# Power.net
KiCad netlist of a schematic drawn in Altium Designer
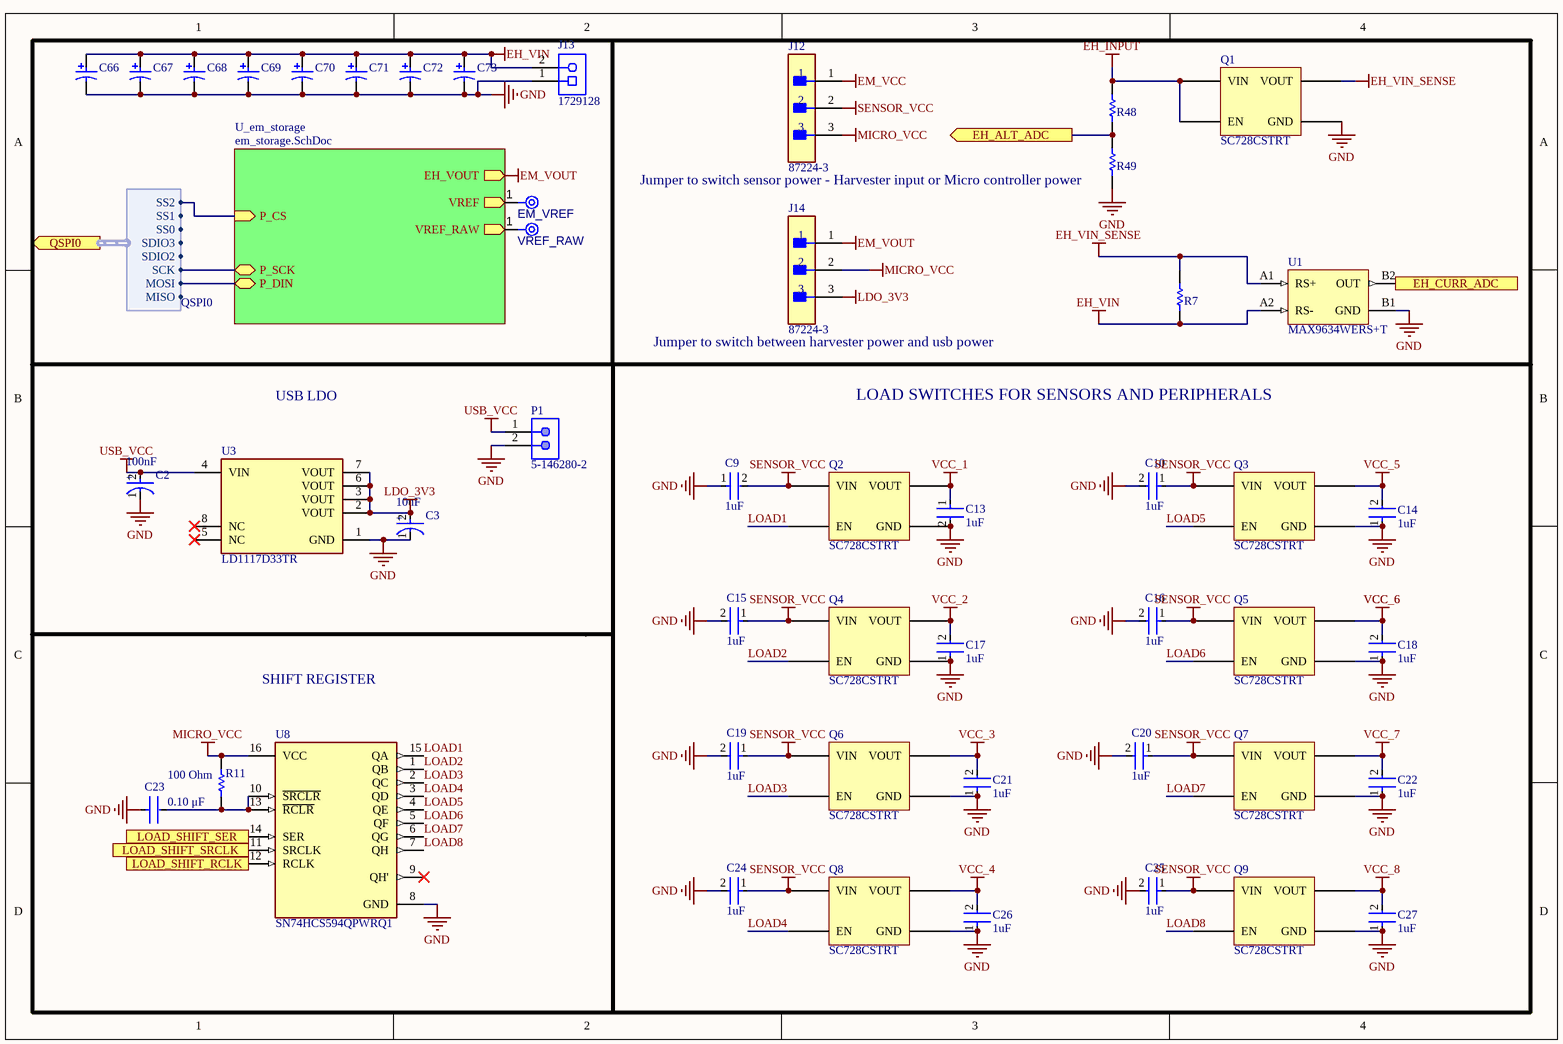
[diagram p0: Power.SchDoc]

(export (version "E")
  (design (tool "Eeschema 10.0.6"))
  (components
    (comp (ref "C2")
      (value "T491A104K035AT")
      (footprint "FP-T491A104K035AT-MFG")
      (description "CAP TANT 0.1UF 10% 35V 1206")
      (fields
        (field (name "TOLERANCE") "10%")
        (field (name "VOLTAGE") "35V")
        (field (name "CAPACITANCE") "100nF")
      )
      (libsource (lib "Altium Content Vault") (part "a00bbbee19879c290e62620ae7e47b1"))
    )
    (comp (ref "C3")
      (value "TAJA106K006RNJ")
      (footprint "FP-TAJA-MFG")
      (description "10uF 6.3V  ±10% 4Ω 1206  SMD Tantalum Capacitor")
      (fields
        (field (name "CAPACITANCE") "10uF")
        (field (name "VOLTAGE") "6.3V")
        (field (name "TOLERANCE") "20%")
      )
      (libsource (lib "Altium Content Vault") (part "203bc49f2ac43e59fd269a8c329ed05"))
    )
    (comp (ref "C9")
      (value "GRT155R61C105KE01J")
      (footprint "FP-GRM15-0_1-MFG")
      (description "CAP CER 1UF 10V X5R 0402")
      (fields
        (field (name "OCTOPART") "https://octopart.com/grm155r61a105ke15d-murata-197442")
        (field (name "MANUFACTURER PART NUMBER") "GRM155R61A105KE15D")
        (field (name "CAPACITANCE") "1uF")
      )
      (libsource (lib "Altium Content Vault") (part "02cd4be3c70576c341d710602a673aa"))
    )
    (comp (ref "C10")
      (value "GRT155R61C105KE01J")
      (footprint "FP-GRM15-0_1-MFG")
      (description "CAP CER 1UF 10V X5R 0402")
      (fields
        (field (name "OCTOPART") "https://octopart.com/grm155r61a105ke15d-murata-197442")
        (field (name "MANUFACTURER PART NUMBER") "GRM155R61A105KE15D")
        (field (name "CAPACITANCE") "1uF")
      )
      (libsource (lib "Altium Content Vault") (part "02cd4be3c70576c341d710602a673aa"))
    )
    (comp (ref "C13")
      (value "GRT155R61C105KE01J")
      (footprint "FP-GRM15-0_1-MFG")
      (description "CAP CER 1UF 10V X5R 0402")
      (fields
        (field (name "OCTOPART") "https://octopart.com/grm155r61a105ke15d-murata-197442")
        (field (name "MANUFACTURER PART NUMBER") "GRM155R61A105KE15D")
        (field (name "CAPACITANCE") "1uF")
      )
      (libsource (lib "Altium Content Vault") (part "02cd4be3c70576c341d710602a673aa"))
    )
    (comp (ref "C14")
      (value "GRT155R61C105KE01J")
      (footprint "FP-GRM15-0_1-MFG")
      (description "CAP CER 1UF 10V X5R 0402")
      (fields
        (field (name "OCTOPART") "https://octopart.com/grm155r61a105ke15d-murata-197442")
        (field (name "MANUFACTURER PART NUMBER") "GRM155R61A105KE15D")
        (field (name "CAPACITANCE") "1uF")
      )
      (libsource (lib "Altium Content Vault") (part "02cd4be3c70576c341d710602a673aa"))
    )
    (comp (ref "C15")
      (value "GRT155R61C105KE01J")
      (footprint "FP-GRM15-0_1-MFG")
      (description "CAP CER 1UF 10V X5R 0402")
      (fields
        (field (name "OCTOPART") "https://octopart.com/grm155r61a105ke15d-murata-197442")
        (field (name "MANUFACTURER PART NUMBER") "GRM155R61A105KE15D")
        (field (name "CAPACITANCE") "1uF")
      )
      (libsource (lib "Altium Content Vault") (part "02cd4be3c70576c341d710602a673aa"))
    )
    (comp (ref "C16")
      (value "GRT155R61C105KE01J")
      (footprint "FP-GRM15-0_1-MFG")
      (description "CAP CER 1UF 10V X5R 0402")
      (fields
        (field (name "OCTOPART") "https://octopart.com/grm155r61a105ke15d-murata-197442")
        (field (name "MANUFACTURER PART NUMBER") "GRM155R61A105KE15D")
        (field (name "CAPACITANCE") "1uF")
      )
      (libsource (lib "Altium Content Vault") (part "02cd4be3c70576c341d710602a673aa"))
    )
    (comp (ref "C17")
      (value "GRT155R61C105KE01J")
      (footprint "FP-GRM15-0_1-MFG")
      (description "CAP CER 1UF 10V X5R 0402")
      (fields
        (field (name "OCTOPART") "https://octopart.com/grm155r61a105ke15d-murata-197442")
        (field (name "MANUFACTURER PART NUMBER") "GRM155R61A105KE15D")
        (field (name "CAPACITANCE") "1uF")
      )
      (libsource (lib "Altium Content Vault") (part "02cd4be3c70576c341d710602a673aa"))
    )
    (comp (ref "C18")
      (value "GRT155R61C105KE01J")
      (footprint "FP-GRM15-0_1-MFG")
      (description "CAP CER 1UF 10V X5R 0402")
      (fields
        (field (name "OCTOPART") "https://octopart.com/grm155r61a105ke15d-murata-197442")
        (field (name "MANUFACTURER PART NUMBER") "GRM155R61A105KE15D")
        (field (name "CAPACITANCE") "1uF")
      )
      (libsource (lib "Altium Content Vault") (part "02cd4be3c70576c341d710602a673aa"))
    )
    (comp (ref "C19")
      (value "GRT155R61C105KE01J")
      (footprint "FP-GRM15-0_1-MFG")
      (description "CAP CER 1UF 10V X5R 0402")
      (fields
        (field (name "OCTOPART") "https://octopart.com/grm155r61a105ke15d-murata-197442")
        (field (name "MANUFACTURER PART NUMBER") "GRM155R61A105KE15D")
        (field (name "CAPACITANCE") "1uF")
      )
      (libsource (lib "Altium Content Vault") (part "02cd4be3c70576c341d710602a673aa"))
    )
    (comp (ref "C20")
      (value "GRT155R61C105KE01J")
      (footprint "FP-GRM15-0_1-MFG")
      (description "CAP CER 1UF 10V X5R 0402")
      (fields
        (field (name "OCTOPART") "https://octopart.com/grm155r61a105ke15d-murata-197442")
        (field (name "MANUFACTURER PART NUMBER") "GRM155R61A105KE15D")
        (field (name "CAPACITANCE") "1uF")
      )
      (libsource (lib "Altium Content Vault") (part "02cd4be3c70576c341d710602a673aa"))
    )
    (comp (ref "C21")
      (value "GRT155R61C105KE01J")
      (footprint "FP-GRM15-0_1-MFG")
      (description "CAP CER 1UF 10V X5R 0402")
      (fields
        (field (name "OCTOPART") "https://octopart.com/grm155r61a105ke15d-murata-197442")
        (field (name "MANUFACTURER PART NUMBER") "GRM155R61A105KE15D")
        (field (name "CAPACITANCE") "1uF")
      )
      (libsource (lib "Altium Content Vault") (part "02cd4be3c70576c341d710602a673aa"))
    )
    (comp (ref "C22")
      (value "GRT155R61C105KE01J")
      (footprint "FP-GRM15-0_1-MFG")
      (description "CAP CER 1UF 10V X5R 0402")
      (fields
        (field (name "OCTOPART") "https://octopart.com/grm155r61a105ke15d-murata-197442")
        (field (name "MANUFACTURER PART NUMBER") "GRM155R61A105KE15D")
        (field (name "CAPACITANCE") "1uF")
      )
      (libsource (lib "Altium Content Vault") (part "02cd4be3c70576c341d710602a673aa"))
    )
    (comp (ref "C23")
      (value "C0402C104K8PACTU")
      (footprint "FP-C0402-BB-MFG")
      (description "CAP CER 0.1UF 10V X5R 0402")
      (fields
        (field (name "CAPACITANCE") "0.10 μF")
        (field (name "MANUFACTURER") "Kemet")
        (field (name "TOLERANCE") "0.1")
      )
      (libsource (lib "Altium Content Vault") (part "b4654b650e69147ec39a6b967a45e02"))
    )
    (comp (ref "C24")
      (value "GRT155R61C105KE01J")
      (footprint "FP-GRM15-0_1-MFG")
      (description "CAP CER 1UF 10V X5R 0402")
      (fields
        (field (name "OCTOPART") "https://octopart.com/grm155r61a105ke15d-murata-197442")
        (field (name "MANUFACTURER PART NUMBER") "GRM155R61A105KE15D")
        (field (name "CAPACITANCE") "1uF")
      )
      (libsource (lib "Altium Content Vault") (part "02cd4be3c70576c341d710602a673aa"))
    )
    (comp (ref "C25")
      (value "GRT155R61C105KE01J")
      (footprint "FP-GRM15-0_1-MFG")
      (description "CAP CER 1UF 10V X5R 0402")
      (fields
        (field (name "OCTOPART") "https://octopart.com/grm155r61a105ke15d-murata-197442")
        (field (name "MANUFACTURER PART NUMBER") "GRM155R61A105KE15D")
        (field (name "CAPACITANCE") "1uF")
      )
      (libsource (lib "Altium Content Vault") (part "02cd4be3c70576c341d710602a673aa"))
    )
    (comp (ref "C26")
      (value "GRT155R61C105KE01J")
      (footprint "FP-GRM15-0_1-MFG")
      (description "CAP CER 1UF 10V X5R 0402")
      (fields
        (field (name "OCTOPART") "https://octopart.com/grm155r61a105ke15d-murata-197442")
        (field (name "MANUFACTURER PART NUMBER") "GRM155R61A105KE15D")
        (field (name "CAPACITANCE") "1uF")
      )
      (libsource (lib "Altium Content Vault") (part "02cd4be3c70576c341d710602a673aa"))
    )
    (comp (ref "C27")
      (value "GRT155R61C105KE01J")
      (footprint "FP-GRM15-0_1-MFG")
      (description "CAP CER 1UF 10V X5R 0402")
      (fields
        (field (name "OCTOPART") "https://octopart.com/grm155r61a105ke15d-murata-197442")
        (field (name "MANUFACTURER PART NUMBER") "GRM155R61A105KE15D")
        (field (name "CAPACITANCE") "1uF")
      )
      (libsource (lib "Altium Content Vault") (part "02cd4be3c70576c341d710602a673aa"))
    )
    (comp (ref "C66")
      (value "T491D106K025AT")
      (footprint "KEMT-T491-D_L")
      (description "Tantalum Capacitor, 10 uF, +/- 10%, 25 V, -55 to 125 degC, 2-Pin SMD, RoHS, Tape and Reel")
      (fields (field (name "MANUFACTURER") "Kemet") (field (name "VOLTAGE") "25VDC"))
      (libsource (lib "Altium Content Vault") (part "CAP-P-2"))
    )
    (comp (ref "C67")
      (value "T491D106K025AT")
      (footprint "KEMT-T491-D_L")
      (description "Tantalum Capacitor, 10 uF, +/- 10%, 25 V, -55 to 125 degC, 2-Pin SMD, RoHS, Tape and Reel")
      (fields (field (name "MANUFACTURER") "Kemet") (field (name "VOLTAGE") "25VDC"))
      (libsource (lib "Altium Content Vault") (part "CAP-P-2"))
    )
    (comp (ref "C68")
      (value "T491D106K025AT")
      (footprint "KEMT-T491-D_L")
      (description "Tantalum Capacitor, 10 uF, +/- 10%, 25 V, -55 to 125 degC, 2-Pin SMD, RoHS, Tape and Reel")
      (fields (field (name "MANUFACTURER") "Kemet") (field (name "VOLTAGE") "25VDC"))
      (libsource (lib "Altium Content Vault") (part "CAP-P-2"))
    )
    (comp (ref "C69")
      (value "T491D106K025AT")
      (footprint "KEMT-T491-D_L")
      (description "Tantalum Capacitor, 10 uF, +/- 10%, 25 V, -55 to 125 degC, 2-Pin SMD, RoHS, Tape and Reel")
      (fields (field (name "MANUFACTURER") "Kemet") (field (name "VOLTAGE") "25VDC"))
      (libsource (lib "Altium Content Vault") (part "CAP-P-2"))
    )
    (comp (ref "C70")
      (value "T491D106K025AT")
      (footprint "KEMT-T491-D_L")
      (description "Tantalum Capacitor, 10 uF, +/- 10%, 25 V, -55 to 125 degC, 2-Pin SMD, RoHS, Tape and Reel")
      (fields (field (name "MANUFACTURER") "Kemet") (field (name "VOLTAGE") "25VDC"))
      (libsource (lib "Altium Content Vault") (part "CAP-P-2"))
    )
    (comp (ref "C71")
      (value "T491D106K025AT")
      (footprint "KEMT-T491-D_L")
      (description "Tantalum Capacitor, 10 uF, +/- 10%, 25 V, -55 to 125 degC, 2-Pin SMD, RoHS, Tape and Reel")
      (fields (field (name "MANUFACTURER") "Kemet") (field (name "VOLTAGE") "25VDC"))
      (libsource (lib "Altium Content Vault") (part "CAP-P-2"))
    )
    (comp (ref "C72")
      (value "T491D106K025AT")
      (footprint "KEMT-T491-D_L")
      (description "Tantalum Capacitor, 10 uF, +/- 10%, 25 V, -55 to 125 degC, 2-Pin SMD, RoHS, Tape and Reel")
      (fields (field (name "MANUFACTURER") "Kemet") (field (name "VOLTAGE") "25VDC"))
      (libsource (lib "Altium Content Vault") (part "CAP-P-2"))
    )
    (comp (ref "C73")
      (value "T491D106K025AT")
      (footprint "KEMT-T491-D_L")
      (description "Tantalum Capacitor, 10 uF, +/- 10%, 25 V, -55 to 125 degC, 2-Pin SMD, RoHS, Tape and Reel")
      (fields (field (name "MANUFACTURER") "Kemet") (field (name "VOLTAGE") "25VDC"))
      (libsource (lib "Altium Content Vault") (part "CAP-P-2"))
    )
    (comp (ref "EM_VREF")
      (value "TPAD6R")
      (footprint "TP06R")
      (description "0.6mm round")
      (libsource (lib "Supersensor") (part "CMP-001-0001-4"))
    )
    (comp (ref "J12")
      (value "87224-3")
      (footprint "FP-87224-3-MFG")
      (description "CONN HEADER VERT 3POS 2.54MM")
      (libsource (lib "Altium Content Vault") (part "0d3f023dd272f625e17a2be33dea85f"))
    )
    (comp (ref "J13")
      (value "1729128")
      (footprint "PHOE-1729128-2_V")
      (description "PCB Terminal Block, 13.5 A, 400 V, 2-Pin THD, RoHS, Bulk")
      (fields (field (name "MANUFACTURER") "Phoenix Contact"))
      (libsource (lib "Altium Content Vault") (part "CN-2P-F-R2"))
    )
    (comp (ref "J14")
      (value "87224-3")
      (footprint "FP-87224-3-MFG")
      (description "CONN HEADER VERT 3POS 2.54MM")
      (libsource (lib "Altium Content Vault") (part "0d3f023dd272f625e17a2be33dea85f"))
    )
    (comp (ref "P1")
      (value "5-146280-2")
      (footprint "TECO-5-146280-2_V")
      (fields (field (name "MANUFACTURER") "TE Connectivity"))
      (libsource (lib "Altium Content Vault") (part "CN-1P-M-R2"))
    )
    (comp (ref "Q1")
      (value "SC728CSTRT")
      (footprint "PCBComponent_1")
      (libsource (lib "Integrated_Library1") (part "SC728CSTRT"))
    )
    (comp (ref "Q2")
      (value "SC728CSTRT")
      (footprint "PCBComponent_1")
      (libsource (lib "Integrated_Library1") (part "SC728CSTRT"))
    )
    (comp (ref "Q3")
      (value "SC728CSTRT")
      (footprint "PCBComponent_1")
      (libsource (lib "Integrated_Library1") (part "SC728CSTRT"))
    )
    (comp (ref "Q4")
      (value "SC728CSTRT")
      (footprint "PCBComponent_1")
      (libsource (lib "Integrated_Library1") (part "SC728CSTRT"))
    )
    (comp (ref "Q5")
      (value "SC728CSTRT")
      (footprint "PCBComponent_1")
      (libsource (lib "Integrated_Library1") (part "SC728CSTRT"))
    )
    (comp (ref "Q6")
      (value "SC728CSTRT")
      (footprint "PCBComponent_1")
      (libsource (lib "Integrated_Library1") (part "SC728CSTRT"))
    )
    (comp (ref "Q7")
      (value "SC728CSTRT")
      (footprint "PCBComponent_1")
      (libsource (lib "Integrated_Library1") (part "SC728CSTRT"))
    )
    (comp (ref "Q8")
      (value "SC728CSTRT")
      (footprint "PCBComponent_1")
      (libsource (lib "Integrated_Library1") (part "SC728CSTRT"))
    )
    (comp (ref "Q9")
      (value "SC728CSTRT")
      (footprint "PCBComponent_1")
      (libsource (lib "Integrated_Library1") (part "SC728CSTRT"))
    )
    (comp (ref "R7")
      (value "WSL0603R0300FEA18")
      (footprint "RESC1508X46X38ML25T25")
      (fields (field (name "MANUFACTURER") "Vishay Dale"))
      (libsource (lib "Altium Content Vault") (part "RES"))
    )
    (comp (ref "R11")
      (value "ERJ-2RKF1000X")
      (footprint "RESC1005X40X25LL05T05")
      (description "Chip Resistor, 100 Ohm, +/- 1%, 100 mW, -55 to 155 degC, 0402 (1005 Metric), RoHS, Tape and Reel")
      (fields
        (field (name "MANUFACTURER") "Basic Passives")
        (field (name "TOLERANCE") "1%")
        (field (name "RESISTANCE") "100 Ohm")
      )
      (libsource (lib "Altium Content Vault") (part "RES-2"))
    )
    (comp (ref "R48")
      (value "RC0402FR-071ML")
      (footprint "RESC1005X40X25NL05T10")
      (description "3M ohm")
      (fields (field (name "MANUFACTURER") "Yageo / Phycomp"))
      (libsource (lib "Altium Content Vault") (part "RES"))
    )
    (comp (ref "R49")
      (value "RC0402FR-071ML")
      (footprint "RESC1005X40X25NL05T10")
      (description "1M ohm")
      (fields (field (name "MANUFACTURER") "Yageo / Phycomp"))
      (libsource (lib "Altium Content Vault") (part "RES"))
    )
    (comp (ref "U1")
      (value "MAX9634WERS+T")
      (footprint "MAXM-R41A1+1")
      (libsource (lib "Altium Content Vault") (part "MAX9938_9634-X4"))
    )
    (comp (ref "U3")
      (value "LD1117D33TR")
      (footprint "FP-SO-8-0016023-MFG")
      (description "IC REG LINEAR 3.3V 800MA 8SO")
      (libsource (lib "Altium Content Vault") (part "79f2e125495cf94f2011e209b176133"))
    )
    (comp (ref "U8")
      (value "SN74HCS594QPWRQ1")
      (footprint "FP-PW0016A-IPC_A")
      (description "AUTOMOTIVE 8-BIT SHIFT REGISTERS")
      (libsource (lib "Altium Content Vault") (part "ee4c9120f52ff91501c7aa2bff67eb2"))
    )
    (comp (ref "VREF_RAW")
      (value "TPAD6R")
      (footprint "TP06R")
      (description "0.6mm round")
      (libsource (lib "Supersensor") (part "CMP-001-0001-4"))
    )
  )
  (nets
    (net (code "2") (name "/EH_ALT_ADC") (class "Default")
      (node (ref "R48") (pin "1") (pinfunction "1_1") (pintype "passive"))
      (node (ref "R49") (pin "2") (pinfunction "2_2") (pintype "passive"))
    )
    (net (code "3") (name "/EH_CURR_ADC") (class "Default")
      (node (ref "U1") (pin "B2") (pinfunction "OUT_B2") (pintype "output"))
    )
    (net (code "4") (name "/LOAD1") (class "Default")
      (node (ref "Q2") (pin "B2") (pinfunction "EN_B2") (pintype "passive"))
      (node (ref "U8") (pin "15") (pinfunction "QA_15") (pintype "output"))
    )
    (net (code "5") (name "/LOAD2") (class "Default")
      (node (ref "Q4") (pin "B2") (pinfunction "EN_B2") (pintype "passive"))
      (node (ref "U8") (pin "1") (pinfunction "QB_1") (pintype "output"))
    )
    (net (code "6") (name "/LOAD3") (class "Default")
      (node (ref "Q6") (pin "B2") (pinfunction "EN_B2") (pintype "passive"))
      (node (ref "U8") (pin "2") (pinfunction "QC_2") (pintype "output"))
    )
    (net (code "7") (name "/LOAD4") (class "Default")
      (node (ref "Q8") (pin "B2") (pinfunction "EN_B2") (pintype "passive"))
      (node (ref "U8") (pin "3") (pinfunction "QD_3") (pintype "output"))
    )
    (net (code "8") (name "/LOAD5") (class "Default")
      (node (ref "Q3") (pin "B2") (pinfunction "EN_B2") (pintype "passive"))
      (node (ref "U8") (pin "4") (pinfunction "QE_4") (pintype "output"))
    )
    (net (code "9") (name "/LOAD6") (class "Default")
      (node (ref "Q5") (pin "B2") (pinfunction "EN_B2") (pintype "passive"))
      (node (ref "U8") (pin "5") (pinfunction "QF_5") (pintype "output"))
    )
    (net (code "10") (name "/LOAD7") (class "Default")
      (node (ref "Q7") (pin "B2") (pinfunction "EN_B2") (pintype "passive"))
      (node (ref "U8") (pin "6") (pinfunction "QG_6") (pintype "output"))
    )
    (net (code "11") (name "/LOAD8") (class "Default")
      (node (ref "Q9") (pin "B2") (pinfunction "EN_B2") (pintype "passive"))
      (node (ref "U8") (pin "7") (pinfunction "QH_7") (pintype "output"))
    )
    (net (code "12") (name "/LOAD_SHIFT_RCLK") (class "Default")
      (node (ref "U8") (pin "12") (pinfunction "RCLK_12") (pintype "input"))
    )
    (net (code "13") (name "/LOAD_SHIFT_SER") (class "Default")
      (node (ref "U8") (pin "14") (pinfunction "SER_14") (pintype "input"))
    )
    (net (code "14") (name "/LOAD_SHIFT_SRCLK") (class "Default")
      (node (ref "U8") (pin "11") (pinfunction "SRCLK_11") (pintype "input"))
    )
    (net (code "18") (name "/VREF") (class "Default")
      (node (ref "EM_VREF") (pin "1") (pinfunction "TP_1") (pintype "passive"))
    )
    (net (code "19") (name "/VREF_RAW") (class "Default")
      (node (ref "VREF_RAW") (pin "1") (pinfunction "TP_1") (pintype "passive"))
    )
    (net (code "21") (name "EH_INPUT") (class "Default")
      (node (ref "Q1") (pin "A2") (pinfunction "VIN_A2") (pintype "passive"))
      (node (ref "Q1") (pin "B2") (pinfunction "EN_B2") (pintype "passive"))
      (node (ref "R48") (pin "2") (pinfunction "2_2") (pintype "passive"))
    )
    (net (code "22") (name "EH_VIN") (class "Default")
      (node (ref "C66") (pin "1") (pinfunction "1_1") (pintype "passive"))
      (node (ref "C67") (pin "1") (pinfunction "1_1") (pintype "passive"))
      (node (ref "C68") (pin "1") (pinfunction "1_1") (pintype "passive"))
      (node (ref "C69") (pin "1") (pinfunction "1_1") (pintype "passive"))
      (node (ref "C70") (pin "1") (pinfunction "1_1") (pintype "passive"))
      (node (ref "C71") (pin "1") (pinfunction "1_1") (pintype "passive"))
      (node (ref "C72") (pin "1") (pinfunction "1_1") (pintype "passive"))
      (node (ref "C73") (pin "1") (pinfunction "1_1") (pintype "passive"))
      (node (ref "J13") (pin "2") (pinfunction "2_2") (pintype "passive"))
      (node (ref "R7") (pin "1") (pinfunction "1_1") (pintype "passive"))
      (node (ref "U1") (pin "A2") (pinfunction "RS-_A2") (pintype "input"))
    )
    (net (code "23") (name "EH_VIN_SENSE") (class "Default")
      (node (ref "Q1") (pin "A1") (pinfunction "VOUT_A1") (pintype "passive"))
      (node (ref "R7") (pin "2") (pinfunction "2_2") (pintype "passive"))
      (node (ref "U1") (pin "A1") (pinfunction "RS+_A1") (pintype "input"))
    )
    (net (code "24") (name "EM_VCC") (class "Default")
      (node (ref "J12") (pin "1") (pinfunction "1_1") (pintype "passive"))
    )
    (net (code "25") (name "EM_VOUT") (class "Default")
      (node (ref "J14") (pin "1") (pinfunction "1_1") (pintype "passive"))
    )
    (net (code "26") (name "GND") (class "Default")
      (node (ref "C10") (pin "2") (pinfunction "2_2") (pintype "passive"))
      (node (ref "C13") (pin "2") (pinfunction "2_2") (pintype "passive"))
      (node (ref "C14") (pin "1") (pinfunction "1_1") (pintype "passive"))
      (node (ref "C15") (pin "2") (pinfunction "2_2") (pintype "passive"))
      (node (ref "C16") (pin "2") (pinfunction "2_2") (pintype "passive"))
      (node (ref "C17") (pin "1") (pinfunction "1_1") (pintype "passive"))
      (node (ref "C18") (pin "1") (pinfunction "1_1") (pintype "passive"))
      (node (ref "C19") (pin "2") (pinfunction "2_2") (pintype "passive"))
      (node (ref "C2") (pin "1") (pinfunction "C_1") (pintype "passive"))
      (node (ref "C20") (pin "2") (pinfunction "2_2") (pintype "passive"))
      (node (ref "C21") (pin "1") (pinfunction "1_1") (pintype "passive"))
      (node (ref "C22") (pin "1") (pinfunction "1_1") (pintype "passive"))
      (node (ref "C23") (pin "1") (pinfunction "1_1") (pintype "passive"))
      (node (ref "C24") (pin "2") (pinfunction "2_2") (pintype "passive"))
      (node (ref "C25") (pin "2") (pinfunction "2_2") (pintype "passive"))
      (node (ref "C26") (pin "1") (pinfunction "1_1") (pintype "passive"))
      (node (ref "C27") (pin "1") (pinfunction "1_1") (pintype "passive"))
      (node (ref "C3") (pin "1") (pinfunction "C_1") (pintype "passive"))
      (node (ref "C66") (pin "2") (pinfunction "2_2") (pintype "passive"))
      (node (ref "C67") (pin "2") (pinfunction "2_2") (pintype "passive"))
      (node (ref "C68") (pin "2") (pinfunction "2_2") (pintype "passive"))
      (node (ref "C69") (pin "2") (pinfunction "2_2") (pintype "passive"))
      (node (ref "C70") (pin "2") (pinfunction "2_2") (pintype "passive"))
      (node (ref "C71") (pin "2") (pinfunction "2_2") (pintype "passive"))
      (node (ref "C72") (pin "2") (pinfunction "2_2") (pintype "passive"))
      (node (ref "C73") (pin "2") (pinfunction "2_2") (pintype "passive"))
      (node (ref "C9") (pin "1") (pinfunction "1_1") (pintype "passive"))
      (node (ref "J13") (pin "1") (pinfunction "1_1") (pintype "passive"))
      (node (ref "P1") (pin "2") (pinfunction "2_2") (pintype "passive"))
      (node (ref "Q1") (pin "B1") (pinfunction "GND_B1") (pintype "passive"))
      (node (ref "Q2") (pin "B1") (pinfunction "GND_B1") (pintype "passive"))
      (node (ref "Q3") (pin "B1") (pinfunction "GND_B1") (pintype "passive"))
      (node (ref "Q4") (pin "B1") (pinfunction "GND_B1") (pintype "passive"))
      (node (ref "Q5") (pin "B1") (pinfunction "GND_B1") (pintype "passive"))
      (node (ref "Q6") (pin "B1") (pinfunction "GND_B1") (pintype "passive"))
      (node (ref "Q7") (pin "B1") (pinfunction "GND_B1") (pintype "passive"))
      (node (ref "Q8") (pin "B1") (pinfunction "GND_B1") (pintype "passive"))
      (node (ref "Q9") (pin "B1") (pinfunction "GND_B1") (pintype "passive"))
      (node (ref "R49") (pin "1") (pinfunction "1_1") (pintype "passive"))
      (node (ref "U1") (pin "B1") (pinfunction "GND_B1") (pintype "power_in"))
      (node (ref "U3") (pin "1") (pinfunction "GND_1") (pintype "power_in"))
      (node (ref "U8") (pin "8") (pinfunction "GND_8") (pintype "power_in"))
    )
    (net (code "27") (name "LDO_3V3") (class "Default")
      (node (ref "C3") (pin "2") (pinfunction "A_2") (pintype "passive"))
      (node (ref "J14") (pin "3") (pinfunction "3_3") (pintype "passive"))
      (node (ref "U3") (pin "2") (pinfunction "VOUT_2") (pintype "power_in"))
      (node (ref "U3") (pin "3") (pinfunction "VOUT_3") (pintype "power_in"))
      (node (ref "U3") (pin "6") (pinfunction "VOUT_6") (pintype "power_in"))
      (node (ref "U3") (pin "7") (pinfunction "VOUT_7") (pintype "power_in"))
    )
    (net (code "28") (name "MICRO_VCC") (class "Default")
      (node (ref "J12") (pin "3") (pinfunction "3_3") (pintype "passive"))
      (node (ref "J14") (pin "2") (pinfunction "2_2") (pintype "passive"))
      (node (ref "R11") (pin "2") (pinfunction "2_2") (pintype "passive"))
      (node (ref "U8") (pin "16") (pinfunction "VCC_16") (pintype "power_in"))
    )
    (net (code "29") (name "Net-(U8-~{RCLR})") (class "Default")
      (node (ref "C23") (pin "2") (pinfunction "2_2") (pintype "passive"))
      (node (ref "R11") (pin "1") (pinfunction "1_1") (pintype "passive"))
      (node (ref "U8") (pin "10") (pinfunction "~{SRCLR}_10") (pintype "input"))
      (node (ref "U8") (pin "13") (pinfunction "~{RCLR}_13") (pintype "input"))
    )
    (net (code "30") (name "SENSOR_VCC") (class "Default")
      (node (ref "C10") (pin "1") (pinfunction "1_1") (pintype "passive"))
      (node (ref "C15") (pin "1") (pinfunction "1_1") (pintype "passive"))
      (node (ref "C16") (pin "1") (pinfunction "1_1") (pintype "passive"))
      (node (ref "C19") (pin "1") (pinfunction "1_1") (pintype "passive"))
      (node (ref "C20") (pin "1") (pinfunction "1_1") (pintype "passive"))
      (node (ref "C24") (pin "1") (pinfunction "1_1") (pintype "passive"))
      (node (ref "C25") (pin "1") (pinfunction "1_1") (pintype "passive"))
      (node (ref "C9") (pin "2") (pinfunction "2_2") (pintype "passive"))
      (node (ref "J12") (pin "2") (pinfunction "2_2") (pintype "passive"))
      (node (ref "Q2") (pin "A2") (pinfunction "VIN_A2") (pintype "passive"))
      (node (ref "Q3") (pin "A2") (pinfunction "VIN_A2") (pintype "passive"))
      (node (ref "Q4") (pin "A2") (pinfunction "VIN_A2") (pintype "passive"))
      (node (ref "Q5") (pin "A2") (pinfunction "VIN_A2") (pintype "passive"))
      (node (ref "Q6") (pin "A2") (pinfunction "VIN_A2") (pintype "passive"))
      (node (ref "Q7") (pin "A2") (pinfunction "VIN_A2") (pintype "passive"))
      (node (ref "Q8") (pin "A2") (pinfunction "VIN_A2") (pintype "passive"))
      (node (ref "Q9") (pin "A2") (pinfunction "VIN_A2") (pintype "passive"))
    )
    (net (code "31") (name "USB_VCC") (class "Default")
      (node (ref "C2") (pin "2") (pinfunction "A_2") (pintype "passive"))
      (node (ref "P1") (pin "1") (pinfunction "1_1") (pintype "passive"))
      (node (ref "U3") (pin "4") (pinfunction "VIN_4") (pintype "power_in"))
    )
    (net (code "32") (name "VCC_1") (class "Default")
      (node (ref "C13") (pin "1") (pinfunction "1_1") (pintype "passive"))
      (node (ref "Q2") (pin "A1") (pinfunction "VOUT_A1") (pintype "passive"))
    )
    (net (code "33") (name "VCC_2") (class "Default")
      (node (ref "C17") (pin "2") (pinfunction "2_2") (pintype "passive"))
      (node (ref "Q4") (pin "A1") (pinfunction "VOUT_A1") (pintype "passive"))
    )
    (net (code "34") (name "VCC_3") (class "Default")
      (node (ref "C21") (pin "2") (pinfunction "2_2") (pintype "passive"))
      (node (ref "Q6") (pin "A1") (pinfunction "VOUT_A1") (pintype "passive"))
    )
    (net (code "35") (name "VCC_4") (class "Default")
      (node (ref "C26") (pin "2") (pinfunction "2_2") (pintype "passive"))
      (node (ref "Q8") (pin "A1") (pinfunction "VOUT_A1") (pintype "passive"))
    )
    (net (code "36") (name "VCC_5") (class "Default")
      (node (ref "C14") (pin "2") (pinfunction "2_2") (pintype "passive"))
      (node (ref "Q3") (pin "A1") (pinfunction "VOUT_A1") (pintype "passive"))
    )
    (net (code "37") (name "VCC_6") (class "Default")
      (node (ref "C18") (pin "2") (pinfunction "2_2") (pintype "passive"))
      (node (ref "Q5") (pin "A1") (pinfunction "VOUT_A1") (pintype "passive"))
    )
    (net (code "38") (name "VCC_7") (class "Default")
      (node (ref "C22") (pin "2") (pinfunction "2_2") (pintype "passive"))
      (node (ref "Q7") (pin "A1") (pinfunction "VOUT_A1") (pintype "passive"))
    )
    (net (code "39") (name "VCC_8") (class "Default")
      (node (ref "C27") (pin "2") (pinfunction "2_2") (pintype "passive"))
      (node (ref "Q9") (pin "A1") (pinfunction "VOUT_A1") (pintype "passive"))
    )
    (net (code "40") (name "unconnected-(U3-NC-Pad5)") (class "Default")
      (node (ref "U3") (pin "5") (pinfunction "NC_5") (pintype "passive+no_connect"))
    )
    (net (code "41") (name "unconnected-(U3-NC-Pad8)") (class "Default")
      (node (ref "U3") (pin "8") (pinfunction "NC_8") (pintype "passive+no_connect"))
    )
    (net (code "42") (name "unconnected-(U8-QH'-Pad9)") (class "Default")
      (node (ref "U8") (pin "9") (pinfunction "QH'_9") (pintype "output+no_connect"))
    )
  )
)
